# Sheet_stand.net
KiCad netlist of a schematic drawn in Altium Designer
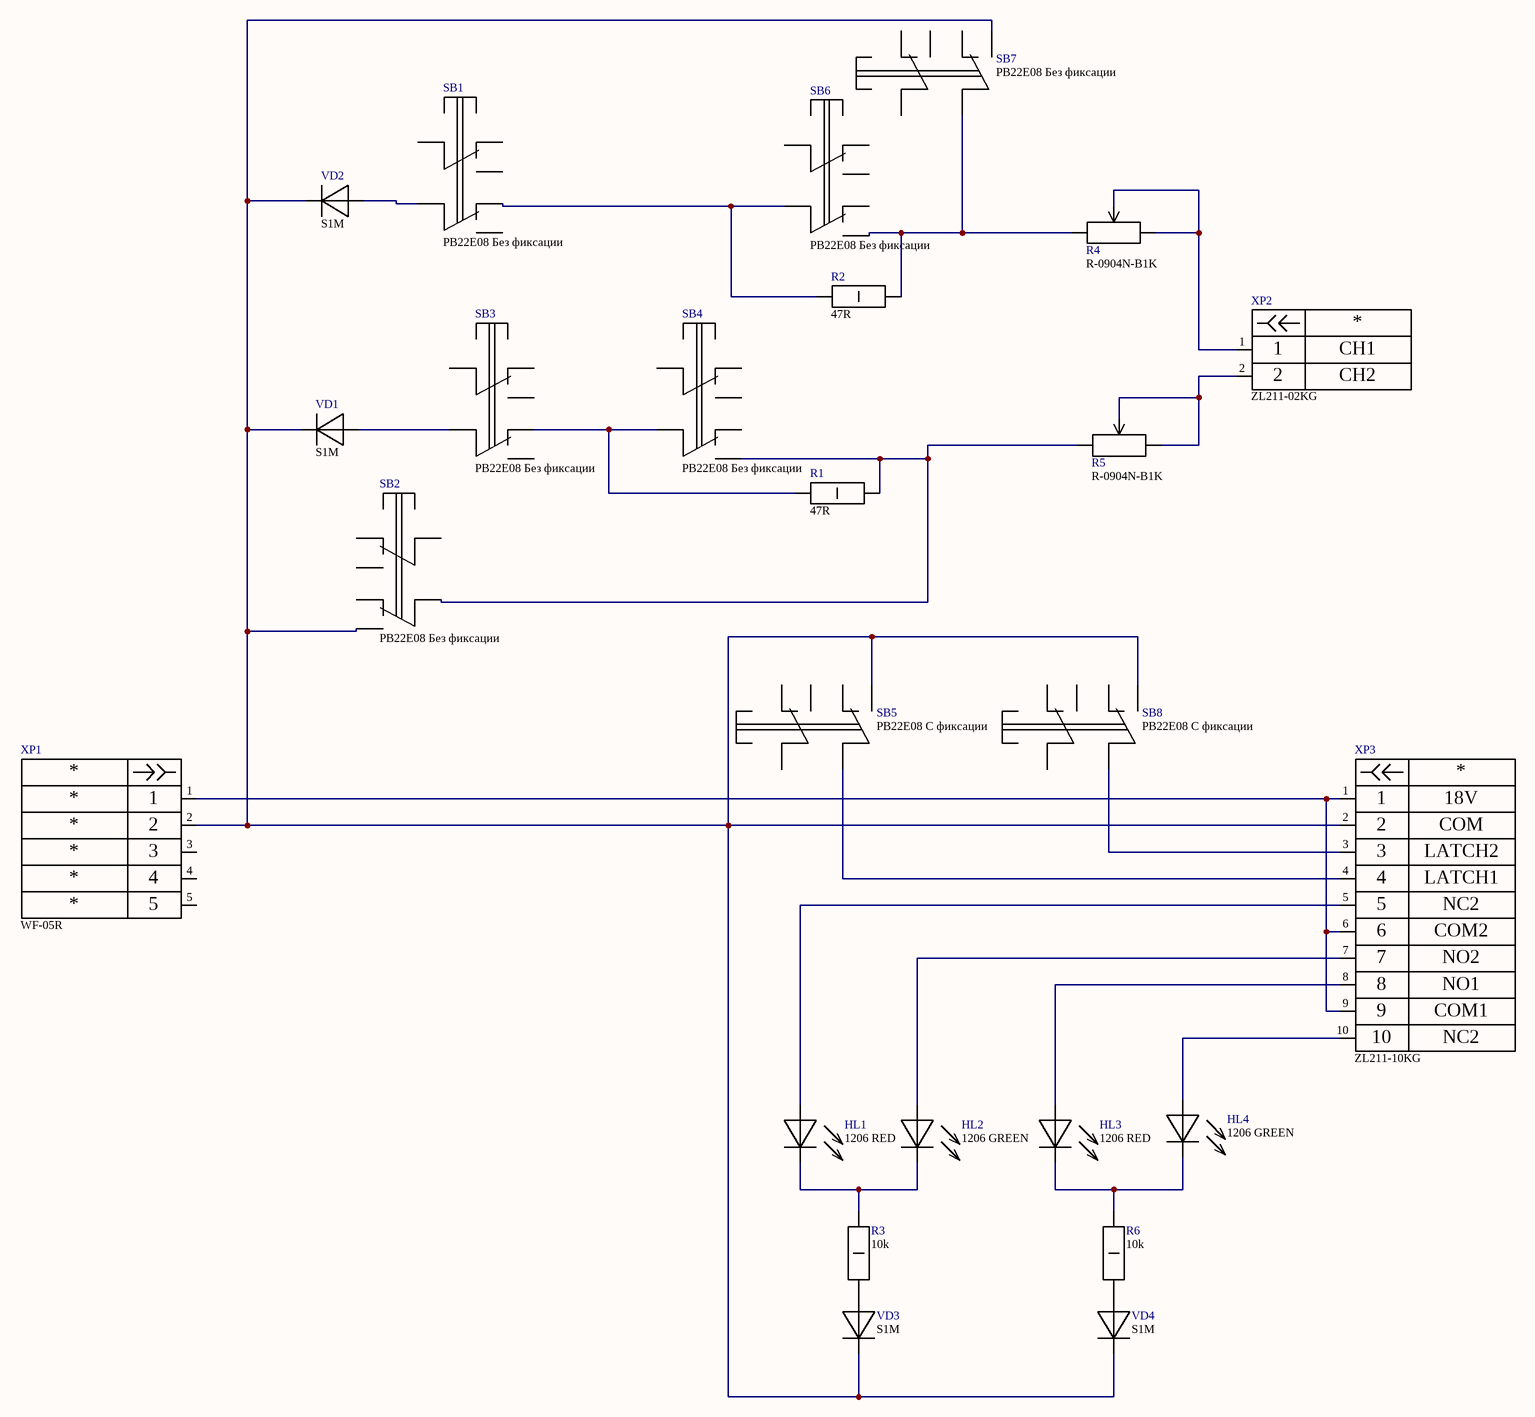
[diagram p0: Sheet_stand.SchDoc]

(export (version "E")
  (design (tool "Eeschema 10.0.6"))
  (components
    (comp (ref "HL1") (value "1206 RED") (footprint "LED 0805") (libsource (lib "Schlib1") (part "LED")))
    (comp (ref "HL2") (value "1206 GREEN") (footprint "LED 0805") (libsource (lib "Schlib1") (part "LED")))
    (comp (ref "HL3") (value "1206 RED") (footprint "LED 0805") (libsource (lib "Schlib1") (part "LED")))
    (comp (ref "HL4") (value "1206 GREEN") (footprint "LED 0805") (libsource (lib "Schlib1") (part "LED")))
    (comp (ref "R1")
      (value "47R")
      (footprint "Resistor 2512")
      (libsource (lib "Schlib1") (part "Resistor 1W"))
    )
    (comp (ref "R2")
      (value "47R")
      (footprint "Resistor 2512")
      (libsource (lib "Schlib1") (part "Resistor 1W"))
    )
    (comp (ref "R3")
      (value "10k")
      (footprint "Resistor 2512")
      (libsource (lib "Schlib1") (part "Resistor 1W"))
    )
    (comp (ref "R4")
      (value "R-0904N-B1K")
      (footprint "R-0904N-B1K")
      (libsource (lib "Schlib1") (part "R-0904N-B1K"))
    )
    (comp (ref "R5")
      (value "R-0904N-B1K")
      (footprint "R-0904N-B1K")
      (libsource (lib "Schlib1") (part "R-0904N-B1K"))
    )
    (comp (ref "R6")
      (value "10k")
      (footprint "Resistor 2512")
      (libsource (lib "Schlib1") (part "Resistor 1W"))
    )
    (comp (ref "SB1")
      (value "PB22E08 Без фиксации")
      (footprint "PB22E08")
      (libsource (lib "Schlib1") (part "PB22E08(Non)"))
    )
    (comp (ref "SB2")
      (value "PB22E08 Без фиксации")
      (footprint "PB22E08")
      (libsource (lib "Schlib1") (part "PB22E08(Non)"))
    )
    (comp (ref "SB3")
      (value "PB22E08 Без фиксации")
      (footprint "PB22E08")
      (libsource (lib "Schlib1") (part "PB22E08(Non)"))
    )
    (comp (ref "SB4")
      (value "PB22E08 Без фиксации")
      (footprint "PB22E08")
      (libsource (lib "Schlib1") (part "PB22E08(Non)"))
    )
    (comp (ref "SB5")
      (value "PB22E08 C фиксации")
      (footprint "PB22E08")
      (libsource (lib "Schlib1") (part "PB22E08"))
    )
    (comp (ref "SB6")
      (value "PB22E08 Без фиксации")
      (footprint "PB22E08")
      (libsource (lib "Schlib1") (part "PB22E08(Non)"))
    )
    (comp (ref "SB7")
      (value "PB22E08 Без фиксации")
      (footprint "PB22E08")
      (libsource (lib "Schlib1") (part "PB22E08(Non)"))
    )
    (comp (ref "SB8")
      (value "PB22E08 C фиксации")
      (footprint "PB22E08")
      (libsource (lib "Schlib1") (part "PB22E08"))
    )
    (comp (ref "VD1") (value "S1M") (footprint "DO-214AC SMA") (libsource (lib "Schlib1") (part "S1M")))
    (comp (ref "VD2") (value "S1M") (footprint "DO-214AC SMA") (libsource (lib "Schlib1") (part "S1M")))
    (comp (ref "VD3") (value "S1M") (footprint "DO-214AC SMA") (libsource (lib "Schlib1") (part "S1M")))
    (comp (ref "VD4") (value "S1M") (footprint "DO-214AC SMA") (libsource (lib "Schlib1") (part "S1M")))
    (comp (ref "XP1")
      (value "WF-05R")
      (footprint "WF-05")
      (fields
        (field (name "NAME1") "*")
        (field (name "NAME") "*")
        (field (name "NAME2") "*")
        (field (name "NAME3") "*")
        (field (name "NAME4") "*")
        (field (name "NAME5") "*")
      )
      (libsource (lib "Россыпь") (part "Pins 1x5"))
    )
    (comp (ref "XP2")
      (value "ZL211-02KG")
      (footprint "Pins 1x2")
      (fields (field (name "NAME1") "CH1") (field (name "NAME") "*") (field (name "NAME2") "CH2"))
      (libsource (lib "Россыпь") (part "Pins 1x2"))
    )
    (comp (ref "XP3")
      (value "ZL211-10KG")
      (footprint "Pins 1x10")
      (fields
        (field (name "NAME1") "18V")
        (field (name "NAME2") "COM")
        (field (name "NAME3") "LATCH2")
        (field (name "NAME") "*")
        (field (name "NAME4") "LATCH1")
        (field (name "NAME5") "NC2")
        (field (name "NAME6") "COM2")
        (field (name "NAME7") "NO2")
        (field (name "NAME8") "NO1")
        (field (name "NAME9") "COM1")
        (field (name "NAME10") "NC2")
      )
      (libsource (lib "Россыпь") (part "Pins 1x10"))
    )
  )
  (nets
    (net (code "1") (name "Net-(HL1-A)") (class "Default")
      (node (ref "HL1") (pin "1") (pinfunction "A_1") (pintype "passive"))
      (node (ref "XP3") (pin "5") (pinfunction "5_5") (pintype "passive"))
    )
    (net (code "2") (name "Net-(HL1-K)") (class "Default")
      (node (ref "HL1") (pin "2") (pinfunction "K_2") (pintype "passive"))
      (node (ref "HL2") (pin "2") (pinfunction "K_2") (pintype "passive"))
      (node (ref "R3") (pin "2") (pinfunction "2_2") (pintype "passive"))
    )
    (net (code "3") (name "Net-(HL2-A)") (class "Default")
      (node (ref "HL2") (pin "1") (pinfunction "A_1") (pintype "passive"))
      (node (ref "XP3") (pin "7") (pinfunction "7_7") (pintype "passive"))
    )
    (net (code "4") (name "Net-(HL3-A)") (class "Default")
      (node (ref "HL3") (pin "1") (pinfunction "A_1") (pintype "passive"))
      (node (ref "XP3") (pin "8") (pinfunction "8_8") (pintype "passive"))
    )
    (net (code "5") (name "Net-(HL3-K)") (class "Default")
      (node (ref "HL3") (pin "2") (pinfunction "K_2") (pintype "passive"))
      (node (ref "HL4") (pin "2") (pinfunction "K_2") (pintype "passive"))
      (node (ref "R6") (pin "2") (pinfunction "2_2") (pintype "passive"))
    )
    (net (code "6") (name "Net-(HL4-A)") (class "Default")
      (node (ref "HL4") (pin "1") (pinfunction "A_1") (pintype "passive"))
      (node (ref "XP3") (pin "10") (pinfunction "10_10") (pintype "passive"))
    )
    (net (code "7") (name "Net-(R1-Pad1)") (class "Default")
      (node (ref "R1") (pin "1") (pinfunction "1_1") (pintype "passive"))
      (node (ref "SB3") (pin "6") (pinfunction "6_6") (pintype "passive"))
      (node (ref "SB4") (pin "4") (pinfunction "4_4") (pintype "passive"))
    )
    (net (code "8") (name "Net-(R1-Pad2)") (class "Default")
      (node (ref "R1") (pin "2") (pinfunction "2_2") (pintype "passive"))
      (node (ref "R5") (pin "1") (pinfunction "1_1") (pintype "passive"))
      (node (ref "SB2") (pin "4") (pinfunction "4_4") (pintype "passive"))
      (node (ref "SB4") (pin "5") (pinfunction "5_5") (pintype "passive"))
    )
    (net (code "9") (name "Net-(R2-Pad1)") (class "Default")
      (node (ref "R2") (pin "1") (pinfunction "1_1") (pintype "passive"))
      (node (ref "SB1") (pin "6") (pinfunction "6_6") (pintype "passive"))
      (node (ref "SB6") (pin "4") (pinfunction "4_4") (pintype "passive"))
    )
    (net (code "10") (name "Net-(R2-Pad2)") (class "Default")
      (node (ref "R2") (pin "2") (pinfunction "2_2") (pintype "passive"))
      (node (ref "R4") (pin "1") (pinfunction "1_1") (pintype "passive"))
      (node (ref "SB6") (pin "5") (pinfunction "5_5") (pintype "passive"))
      (node (ref "SB7") (pin "4") (pinfunction "4_4") (pintype "passive"))
    )
    (net (code "11") (name "Net-(R4-Pad2)") (class "Default")
      (node (ref "R4") (pin "2") (pinfunction "2_2") (pintype "passive"))
      (node (ref "R4") (pin "3") (pinfunction "3_3") (pintype "passive"))
      (node (ref "XP2") (pin "1") (pinfunction "1_1") (pintype "passive"))
    )
    (net (code "12") (name "Net-(R5-Pad2)") (class "Default")
      (node (ref "R5") (pin "2") (pinfunction "2_2") (pintype "passive"))
      (node (ref "R5") (pin "3") (pinfunction "3_3") (pintype "passive"))
      (node (ref "XP2") (pin "2") (pinfunction "2_2") (pintype "passive"))
    )
    (net (code "13") (name "Net-(SB5-Pad4)") (class "Default")
      (node (ref "SB5") (pin "4") (pinfunction "4_4") (pintype "passive"))
      (node (ref "XP3") (pin "4") (pinfunction "4_4") (pintype "passive"))
    )
    (net (code "14") (name "Net-(SB8-Pad4)") (class "Default")
      (node (ref "SB8") (pin "4") (pinfunction "4_4") (pintype "passive"))
      (node (ref "XP3") (pin "3") (pinfunction "3_3") (pintype "passive"))
    )
    (net (code "15") (name "Net-(VD1-A)") (class "Default")
      (node (ref "SB3") (pin "4") (pinfunction "4_4") (pintype "passive"))
      (node (ref "VD1") (pin "1") (pinfunction "A_1") (pintype "passive"))
    )
    (net (code "16") (name "Net-(VD1-K)") (class "Default")
      (node (ref "SB2") (pin "5") (pinfunction "5_5") (pintype "passive"))
      (node (ref "SB5") (pin "5") (pinfunction "5_5") (pintype "passive"))
      (node (ref "SB7") (pin "5") (pinfunction "5_5") (pintype "passive"))
      (node (ref "SB8") (pin "5") (pinfunction "5_5") (pintype "passive"))
      (node (ref "VD1") (pin "2") (pinfunction "K_2") (pintype "passive"))
      (node (ref "VD2") (pin "2") (pinfunction "K_2") (pintype "passive"))
      (node (ref "VD3") (pin "2") (pinfunction "K_2") (pintype "passive"))
      (node (ref "VD4") (pin "2") (pinfunction "K_2") (pintype "passive"))
      (node (ref "XP1") (pin "2") (pinfunction "2_2") (pintype "passive"))
      (node (ref "XP3") (pin "2") (pinfunction "2_2") (pintype "passive"))
    )
    (net (code "17") (name "Net-(VD2-A)") (class "Default")
      (node (ref "SB1") (pin "4") (pinfunction "4_4") (pintype "passive"))
      (node (ref "VD2") (pin "1") (pinfunction "A_1") (pintype "passive"))
    )
    (net (code "18") (name "Net-(VD3-A)") (class "Default")
      (node (ref "R3") (pin "1") (pinfunction "1_1") (pintype "passive"))
      (node (ref "VD3") (pin "1") (pinfunction "A_1") (pintype "passive"))
    )
    (net (code "19") (name "Net-(VD4-A)") (class "Default")
      (node (ref "R6") (pin "1") (pinfunction "1_1") (pintype "passive"))
      (node (ref "VD4") (pin "1") (pinfunction "A_1") (pintype "passive"))
    )
    (net (code "20") (name "Net-(XP1-Pad1)") (class "Default")
      (node (ref "XP1") (pin "1") (pinfunction "1_1") (pintype "passive"))
      (node (ref "XP3") (pin "1") (pinfunction "1_1") (pintype "passive"))
      (node (ref "XP3") (pin "6") (pinfunction "6_6") (pintype "passive"))
      (node (ref "XP3") (pin "9") (pinfunction "9_9") (pintype "passive"))
    )
    (net (code "21") (name "unconnected-(SB1-Pad1)") (class "Default")
      (node (ref "SB1") (pin "1") (pinfunction "1_1") (pintype "passive"))
    )
    (net (code "22") (name "unconnected-(SB1-Pad2)") (class "Default")
      (node (ref "SB1") (pin "2") (pinfunction "2_2") (pintype "passive"))
    )
    (net (code "23") (name "unconnected-(SB1-Pad3)") (class "Default")
      (node (ref "SB1") (pin "3") (pinfunction "3_3") (pintype "passive"))
    )
    (net (code "24") (name "unconnected-(SB1-Pad5)") (class "Default")
      (node (ref "SB1") (pin "5") (pinfunction "5_5") (pintype "passive"))
    )
    (net (code "25") (name "unconnected-(SB2-Pad1)") (class "Default")
      (node (ref "SB2") (pin "1") (pinfunction "1_1") (pintype "passive"))
    )
    (net (code "26") (name "unconnected-(SB2-Pad2)") (class "Default")
      (node (ref "SB2") (pin "2") (pinfunction "2_2") (pintype "passive"))
    )
    (net (code "27") (name "unconnected-(SB2-Pad3)") (class "Default")
      (node (ref "SB2") (pin "3") (pinfunction "3_3") (pintype "passive"))
    )
    (net (code "28") (name "unconnected-(SB2-Pad6)") (class "Default")
      (node (ref "SB2") (pin "6") (pinfunction "6_6") (pintype "passive"))
    )
    (net (code "29") (name "unconnected-(SB3-Pad1)") (class "Default")
      (node (ref "SB3") (pin "1") (pinfunction "1_1") (pintype "passive"))
    )
    (net (code "30") (name "unconnected-(SB3-Pad2)") (class "Default")
      (node (ref "SB3") (pin "2") (pinfunction "2_2") (pintype "passive"))
    )
    (net (code "31") (name "unconnected-(SB3-Pad3)") (class "Default")
      (node (ref "SB3") (pin "3") (pinfunction "3_3") (pintype "passive"))
    )
    (net (code "32") (name "unconnected-(SB3-Pad5)") (class "Default")
      (node (ref "SB3") (pin "5") (pinfunction "5_5") (pintype "passive"))
    )
    (net (code "33") (name "unconnected-(SB4-Pad1)") (class "Default")
      (node (ref "SB4") (pin "1") (pinfunction "1_1") (pintype "passive"))
    )
    (net (code "34") (name "unconnected-(SB4-Pad2)") (class "Default")
      (node (ref "SB4") (pin "2") (pinfunction "2_2") (pintype "passive"))
    )
    (net (code "35") (name "unconnected-(SB4-Pad3)") (class "Default")
      (node (ref "SB4") (pin "3") (pinfunction "3_3") (pintype "passive"))
    )
    (net (code "36") (name "unconnected-(SB4-Pad6)") (class "Default")
      (node (ref "SB4") (pin "6") (pinfunction "6_6") (pintype "passive"))
    )
    (net (code "37") (name "unconnected-(SB5-Pad1)") (class "Default")
      (node (ref "SB5") (pin "1") (pinfunction "1_1") (pintype "passive"))
    )
    (net (code "38") (name "unconnected-(SB5-Pad2)") (class "Default")
      (node (ref "SB5") (pin "2") (pinfunction "2_2") (pintype "passive"))
    )
    (net (code "39") (name "unconnected-(SB5-Pad3)") (class "Default")
      (node (ref "SB5") (pin "3") (pinfunction "3_3") (pintype "passive"))
    )
    (net (code "40") (name "unconnected-(SB5-Pad6)") (class "Default")
      (node (ref "SB5") (pin "6") (pinfunction "6_6") (pintype "passive"))
    )
    (net (code "41") (name "unconnected-(SB6-Pad1)") (class "Default")
      (node (ref "SB6") (pin "1") (pinfunction "1_1") (pintype "passive"))
    )
    (net (code "42") (name "unconnected-(SB6-Pad2)") (class "Default")
      (node (ref "SB6") (pin "2") (pinfunction "2_2") (pintype "passive"))
    )
    (net (code "43") (name "unconnected-(SB6-Pad3)") (class "Default")
      (node (ref "SB6") (pin "3") (pinfunction "3_3") (pintype "passive"))
    )
    (net (code "44") (name "unconnected-(SB6-Pad6)") (class "Default")
      (node (ref "SB6") (pin "6") (pinfunction "6_6") (pintype "passive"))
    )
    (net (code "45") (name "unconnected-(SB7-Pad1)") (class "Default")
      (node (ref "SB7") (pin "1") (pinfunction "1_1") (pintype "passive"))
    )
    (net (code "46") (name "unconnected-(SB7-Pad2)") (class "Default")
      (node (ref "SB7") (pin "2") (pinfunction "2_2") (pintype "passive"))
    )
    (net (code "47") (name "unconnected-(SB7-Pad3)") (class "Default")
      (node (ref "SB7") (pin "3") (pinfunction "3_3") (pintype "passive"))
    )
    (net (code "48") (name "unconnected-(SB7-Pad6)") (class "Default")
      (node (ref "SB7") (pin "6") (pinfunction "6_6") (pintype "passive"))
    )
    (net (code "49") (name "unconnected-(SB8-Pad1)") (class "Default")
      (node (ref "SB8") (pin "1") (pinfunction "1_1") (pintype "passive"))
    )
    (net (code "50") (name "unconnected-(SB8-Pad2)") (class "Default")
      (node (ref "SB8") (pin "2") (pinfunction "2_2") (pintype "passive"))
    )
    (net (code "51") (name "unconnected-(SB8-Pad3)") (class "Default")
      (node (ref "SB8") (pin "3") (pinfunction "3_3") (pintype "passive"))
    )
    (net (code "52") (name "unconnected-(SB8-Pad6)") (class "Default")
      (node (ref "SB8") (pin "6") (pinfunction "6_6") (pintype "passive"))
    )
    (net (code "53") (name "unconnected-(XP1-Pad3)") (class "Default")
      (node (ref "XP1") (pin "3") (pinfunction "3_3") (pintype "passive"))
    )
    (net (code "54") (name "unconnected-(XP1-Pad4)") (class "Default")
      (node (ref "XP1") (pin "4") (pinfunction "4_4") (pintype "passive"))
    )
    (net (code "55") (name "unconnected-(XP1-Pad5)") (class "Default")
      (node (ref "XP1") (pin "5") (pinfunction "5_5") (pintype "passive"))
    )
  )
)
